# MobileArcade.net
KiCad netlist of a schematic drawn in EAGLE
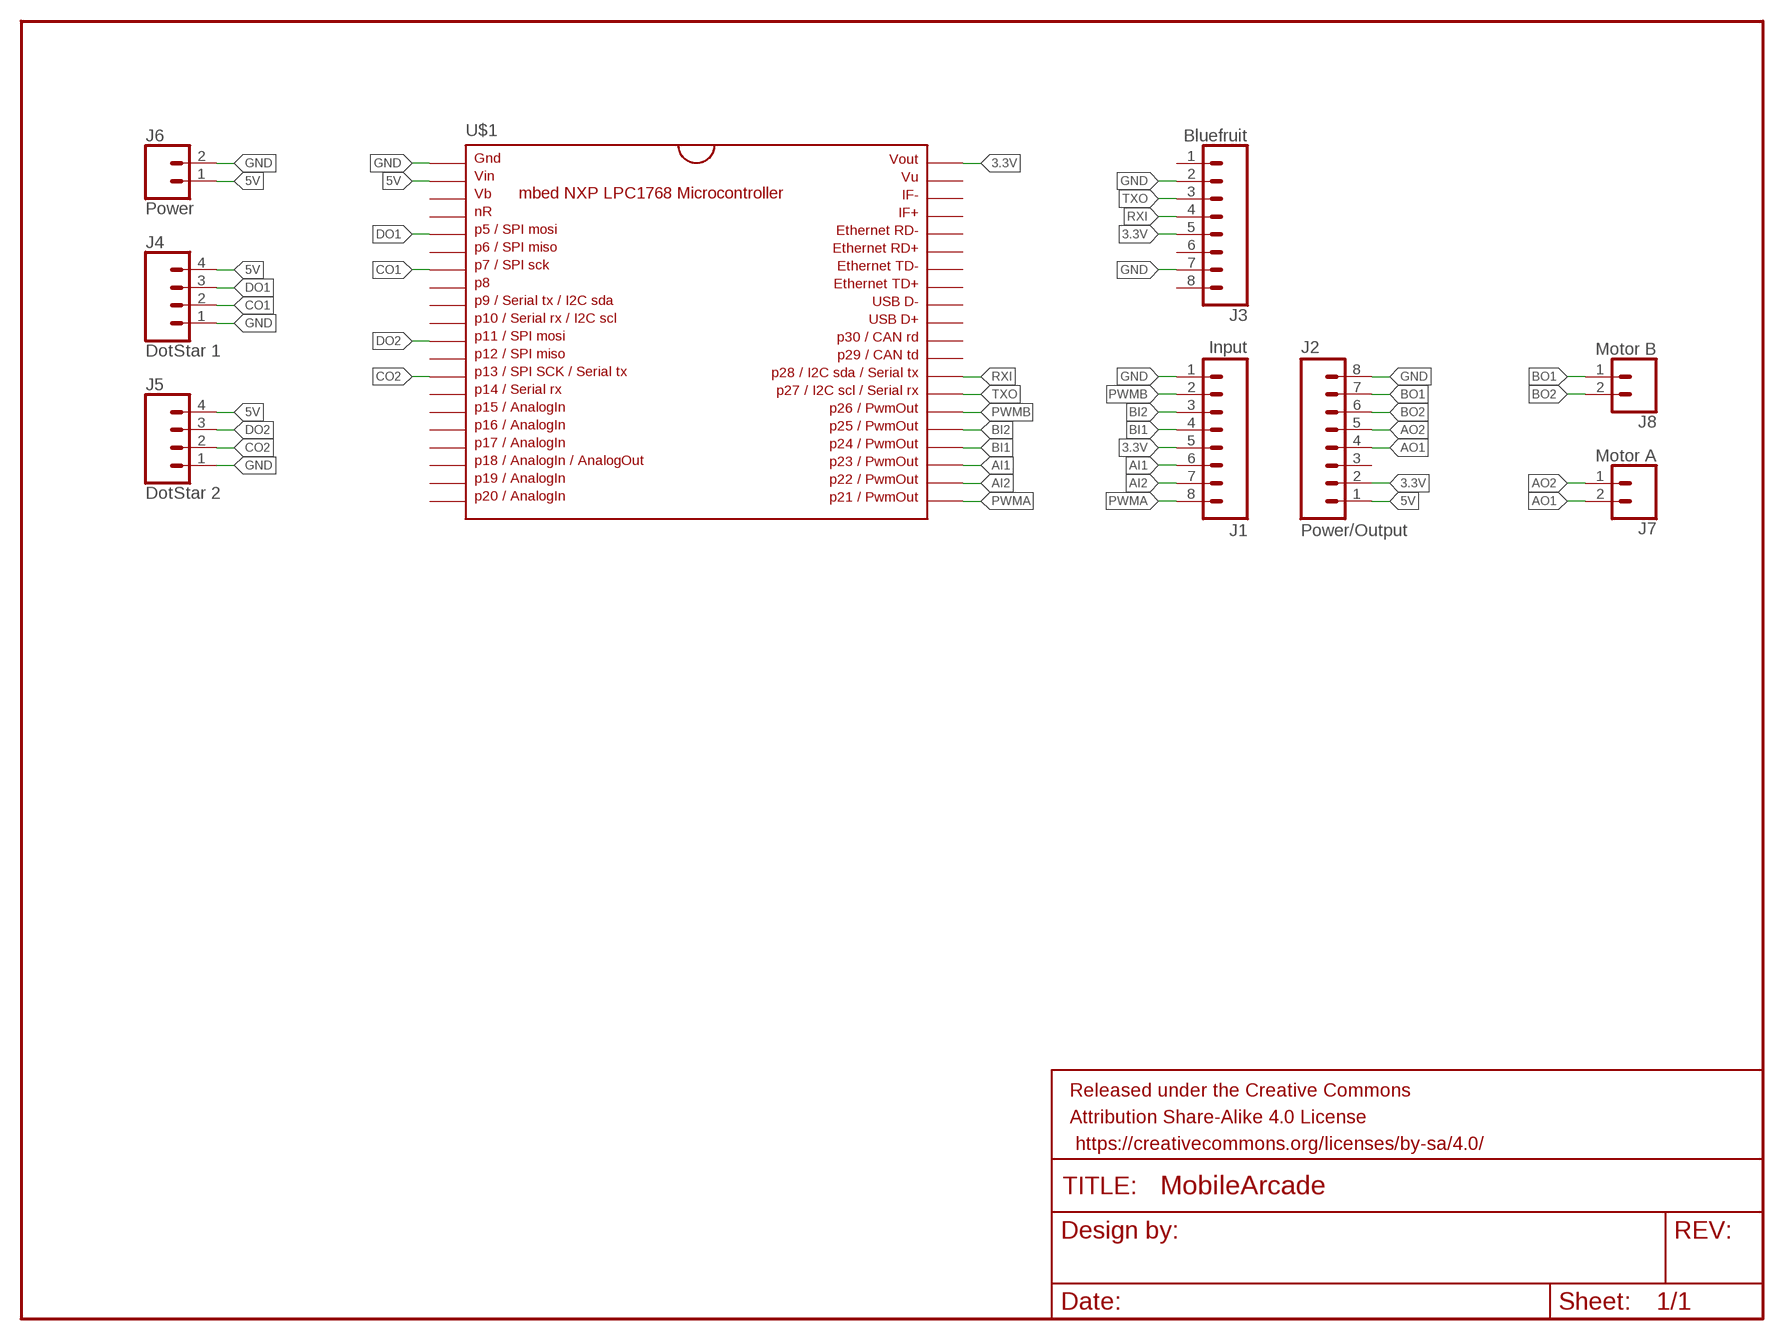
[diagram p0: schematic, sheet 1]

(export (version "E")
  (design (tool "Eeschema 10.0.6"))
  (components
    (comp (ref "FRAME1")
      (value "FRAME-LETTERNO_PACKAGE")
      (footprint "eagle-import:DUMMY")
      (fields (field (name "DESIGNER") "Nobody"))
      (libsource (lib "eagle-import") (part "FRAME-LETTERNO_PACKAGE"))
    )
    (comp (ref "J1")
      (value "Input")
      (footprint "eagle-import:1X08")
      (libsource (lib "eagle-import") (part "CONN_08{dblquote}"))
    )
    (comp (ref "J2")
      (value "Power/Output")
      (footprint "eagle-import:1X08")
      (libsource (lib "eagle-import") (part "CONN_08{dblquote}"))
    )
    (comp (ref "J3")
      (value "Bluefruit")
      (footprint "eagle-import:1X08")
      (libsource (lib "eagle-import") (part "CONN_08{dblquote}"))
    )
    (comp (ref "J4")
      (value "DotStar 1")
      (footprint "eagle-import:1X04")
      (libsource (lib "eagle-import") (part "CONN_04"))
    )
    (comp (ref "J5")
      (value "DotStar 2")
      (footprint "eagle-import:1X04")
      (libsource (lib "eagle-import") (part "CONN_04"))
    )
    (comp (ref "J6")
      (value "Power")
      (footprint "eagle-import:1X02")
      (libsource (lib "eagle-import") (part "CONN_02"))
    )
    (comp (ref "J7")
      (value "Motor A")
      (footprint "eagle-import:1X02")
      (libsource (lib "eagle-import") (part "CONN_02"))
    )
    (comp (ref "J8")
      (value "Motor B")
      (footprint "eagle-import:1X02")
      (libsource (lib "eagle-import") (part "CONN_02"))
    )
    (comp (ref "U$1")
      (value "MBED1768")
      (footprint "eagle-import:DIL40_0.9")
      (libsource (lib "eagle-import") (part "MBED_NXP_LPC1768"))
    )
  )
  (nets
    (net (code "1") (name "3.3V") (class "Default")
      (node (ref "J1") (pin "5") (pinfunction "5_5") (pintype "passive"))
      (node (ref "J2") (pin "2") (pinfunction "2_2") (pintype "passive"))
      (node (ref "J3") (pin "5") (pinfunction "5_5") (pintype "passive"))
      (node (ref "U$1") (pin "40") (pinfunction "P$40_40") (pintype "bidirectional"))
    )
    (net (code "2") (name "5V") (class "Default")
      (node (ref "J2") (pin "1") (pinfunction "1_1") (pintype "passive"))
      (node (ref "J4") (pin "4") (pinfunction "4_4") (pintype "passive"))
      (node (ref "J5") (pin "4") (pinfunction "4_4") (pintype "passive"))
      (node (ref "J6") (pin "1") (pinfunction "1_1") (pintype "passive"))
      (node (ref "U$1") (pin "2") (pinfunction "P$2_2") (pintype "bidirectional"))
    )
    (net (code "3") (name "AI1") (class "Default")
      (node (ref "J1") (pin "6") (pinfunction "6_6") (pintype "passive"))
      (node (ref "U$1") (pin "23") (pinfunction "P$23_23") (pintype "bidirectional"))
    )
    (net (code "4") (name "AI2") (class "Default")
      (node (ref "J1") (pin "7") (pinfunction "7_7") (pintype "passive"))
      (node (ref "U$1") (pin "22") (pinfunction "P$22_22") (pintype "bidirectional"))
    )
    (net (code "5") (name "AO1") (class "Default")
      (node (ref "J2") (pin "4") (pinfunction "4_4") (pintype "passive"))
      (node (ref "J7") (pin "2") (pinfunction "2_2") (pintype "passive"))
    )
    (net (code "6") (name "AO2") (class "Default")
      (node (ref "J2") (pin "5") (pinfunction "5_5") (pintype "passive"))
      (node (ref "J7") (pin "1") (pinfunction "1_1") (pintype "passive"))
    )
    (net (code "7") (name "BI1") (class "Default")
      (node (ref "J1") (pin "4") (pinfunction "4_4") (pintype "passive"))
      (node (ref "U$1") (pin "24") (pinfunction "P$24_24") (pintype "bidirectional"))
    )
    (net (code "8") (name "BI2") (class "Default")
      (node (ref "J1") (pin "3") (pinfunction "3_3") (pintype "passive"))
      (node (ref "U$1") (pin "25") (pinfunction "P$25_25") (pintype "bidirectional"))
    )
    (net (code "9") (name "BO1") (class "Default")
      (node (ref "J2") (pin "7") (pinfunction "7_7") (pintype "passive"))
      (node (ref "J8") (pin "1") (pinfunction "1_1") (pintype "passive"))
    )
    (net (code "10") (name "BO2") (class "Default")
      (node (ref "J2") (pin "6") (pinfunction "6_6") (pintype "passive"))
      (node (ref "J8") (pin "2") (pinfunction "2_2") (pintype "passive"))
    )
    (net (code "11") (name "CO1") (class "Default")
      (node (ref "J4") (pin "2") (pinfunction "2_2") (pintype "passive"))
      (node (ref "U$1") (pin "7") (pinfunction "P$7_7") (pintype "bidirectional"))
    )
    (net (code "12") (name "CO2") (class "Default")
      (node (ref "J5") (pin "2") (pinfunction "2_2") (pintype "passive"))
      (node (ref "U$1") (pin "13") (pinfunction "P$13_13") (pintype "bidirectional"))
    )
    (net (code "13") (name "DO1") (class "Default")
      (node (ref "J4") (pin "3") (pinfunction "3_3") (pintype "passive"))
      (node (ref "U$1") (pin "5") (pinfunction "P$5_5") (pintype "bidirectional"))
    )
    (net (code "14") (name "DO2") (class "Default")
      (node (ref "J5") (pin "3") (pinfunction "3_3") (pintype "passive"))
      (node (ref "U$1") (pin "11") (pinfunction "P$11_11") (pintype "bidirectional"))
    )
    (net (code "15") (name "GND") (class "Default")
      (node (ref "J1") (pin "1") (pinfunction "1_1") (pintype "passive"))
      (node (ref "J2") (pin "8") (pinfunction "8_8") (pintype "passive"))
      (node (ref "J3") (pin "2") (pinfunction "2_2") (pintype "passive"))
      (node (ref "J3") (pin "7") (pinfunction "7_7") (pintype "passive"))
      (node (ref "J4") (pin "1") (pinfunction "1_1") (pintype "passive"))
      (node (ref "J5") (pin "1") (pinfunction "1_1") (pintype "passive"))
      (node (ref "J6") (pin "2") (pinfunction "2_2") (pintype "passive"))
      (node (ref "U$1") (pin "1") (pinfunction "P$1_1") (pintype "bidirectional"))
    )
    (net (code "16") (name "PWMA") (class "Default")
      (node (ref "J1") (pin "8") (pinfunction "8_8") (pintype "passive"))
      (node (ref "U$1") (pin "21") (pinfunction "P$21_21") (pintype "bidirectional"))
    )
    (net (code "17") (name "PWMB") (class "Default")
      (node (ref "J1") (pin "2") (pinfunction "2_2") (pintype "passive"))
      (node (ref "U$1") (pin "26") (pinfunction "P$26_26") (pintype "bidirectional"))
    )
    (net (code "18") (name "RXI") (class "Default")
      (node (ref "J3") (pin "4") (pinfunction "4_4") (pintype "passive"))
      (node (ref "U$1") (pin "28") (pinfunction "P$28_28") (pintype "bidirectional"))
    )
    (net (code "19") (name "TXO") (class "Default")
      (node (ref "J3") (pin "3") (pinfunction "3_3") (pintype "passive"))
      (node (ref "U$1") (pin "27") (pinfunction "P$27_27") (pintype "bidirectional"))
    )
    (net (code "20") (name "unconnected-(J2-Pad3)") (class "Default")
      (node (ref "J2") (pin "3") (pinfunction "3_3") (pintype "passive"))
    )
    (net (code "21") (name "unconnected-(J3-Pad1)") (class "Default")
      (node (ref "J3") (pin "1") (pinfunction "1_1") (pintype "passive"))
    )
    (net (code "22") (name "unconnected-(J3-Pad6)") (class "Default")
      (node (ref "J3") (pin "6") (pinfunction "6_6") (pintype "passive"))
    )
    (net (code "23") (name "unconnected-(J3-Pad8)") (class "Default")
      (node (ref "J3") (pin "8") (pinfunction "8_8") (pintype "passive"))
    )
    (net (code "24") (name "unconnected-(U$1-P$3-Pad3)") (class "Default")
      (node (ref "U$1") (pin "3") (pinfunction "P$3_3") (pintype "bidirectional"))
    )
    (net (code "25") (name "unconnected-(U$1-P$4-Pad4)") (class "Default")
      (node (ref "U$1") (pin "4") (pinfunction "P$4_4") (pintype "bidirectional"))
    )
    (net (code "26") (name "unconnected-(U$1-P$6-Pad6)") (class "Default")
      (node (ref "U$1") (pin "6") (pinfunction "P$6_6") (pintype "bidirectional"))
    )
    (net (code "27") (name "unconnected-(U$1-P$8-Pad8)") (class "Default")
      (node (ref "U$1") (pin "8") (pinfunction "P$8_8") (pintype "bidirectional"))
    )
    (net (code "28") (name "unconnected-(U$1-P$9-Pad9)") (class "Default")
      (node (ref "U$1") (pin "9") (pinfunction "P$9_9") (pintype "bidirectional"))
    )
    (net (code "29") (name "unconnected-(U$1-P$10-Pad10)") (class "Default")
      (node (ref "U$1") (pin "10") (pinfunction "P$10_10") (pintype "bidirectional"))
    )
    (net (code "30") (name "unconnected-(U$1-P$12-Pad12)") (class "Default")
      (node (ref "U$1") (pin "12") (pinfunction "P$12_12") (pintype "bidirectional"))
    )
    (net (code "31") (name "unconnected-(U$1-P$14-Pad14)") (class "Default")
      (node (ref "U$1") (pin "14") (pinfunction "P$14_14") (pintype "bidirectional"))
    )
    (net (code "32") (name "unconnected-(U$1-P$15-Pad15)") (class "Default")
      (node (ref "U$1") (pin "15") (pinfunction "P$15_15") (pintype "bidirectional"))
    )
    (net (code "33") (name "unconnected-(U$1-P$16-Pad16)") (class "Default")
      (node (ref "U$1") (pin "16") (pinfunction "P$16_16") (pintype "bidirectional"))
    )
    (net (code "34") (name "unconnected-(U$1-P$17-Pad17)") (class "Default")
      (node (ref "U$1") (pin "17") (pinfunction "P$17_17") (pintype "bidirectional"))
    )
    (net (code "35") (name "unconnected-(U$1-P$18-Pad18)") (class "Default")
      (node (ref "U$1") (pin "18") (pinfunction "P$18_18") (pintype "bidirectional"))
    )
    (net (code "36") (name "unconnected-(U$1-P$19-Pad19)") (class "Default")
      (node (ref "U$1") (pin "19") (pinfunction "P$19_19") (pintype "bidirectional"))
    )
    (net (code "37") (name "unconnected-(U$1-P$20-Pad20)") (class "Default")
      (node (ref "U$1") (pin "20") (pinfunction "P$20_20") (pintype "bidirectional"))
    )
    (net (code "38") (name "unconnected-(U$1-P$29-Pad29)") (class "Default")
      (node (ref "U$1") (pin "29") (pinfunction "P$29_29") (pintype "bidirectional"))
    )
    (net (code "39") (name "unconnected-(U$1-P$30-Pad30)") (class "Default")
      (node (ref "U$1") (pin "30") (pinfunction "P$30_30") (pintype "bidirectional"))
    )
    (net (code "40") (name "unconnected-(U$1-P$31-Pad31)") (class "Default")
      (node (ref "U$1") (pin "31") (pinfunction "P$31_31") (pintype "bidirectional"))
    )
    (net (code "41") (name "unconnected-(U$1-P$32-Pad32)") (class "Default")
      (node (ref "U$1") (pin "32") (pinfunction "P$32_32") (pintype "bidirectional"))
    )
    (net (code "42") (name "unconnected-(U$1-P$33-Pad33)") (class "Default")
      (node (ref "U$1") (pin "33") (pinfunction "P$33_33") (pintype "bidirectional"))
    )
    (net (code "43") (name "unconnected-(U$1-P$34-Pad34)") (class "Default")
      (node (ref "U$1") (pin "34") (pinfunction "P$34_34") (pintype "bidirectional"))
    )
    (net (code "44") (name "unconnected-(U$1-P$35-Pad35)") (class "Default")
      (node (ref "U$1") (pin "35") (pinfunction "P$35_35") (pintype "bidirectional"))
    )
    (net (code "45") (name "unconnected-(U$1-P$36-Pad36)") (class "Default")
      (node (ref "U$1") (pin "36") (pinfunction "P$36_36") (pintype "bidirectional"))
    )
    (net (code "46") (name "unconnected-(U$1-P$37-Pad37)") (class "Default")
      (node (ref "U$1") (pin "37") (pinfunction "P$37_37") (pintype "bidirectional"))
    )
    (net (code "47") (name "unconnected-(U$1-P$38-Pad38)") (class "Default")
      (node (ref "U$1") (pin "38") (pinfunction "P$38_38") (pintype "bidirectional"))
    )
    (net (code "48") (name "unconnected-(U$1-P$39-Pad39)") (class "Default")
      (node (ref "U$1") (pin "39") (pinfunction "P$39_39") (pintype "bidirectional"))
    )
  )
)
